# Power.net
KiCad netlist of a schematic drawn in Altium Designer
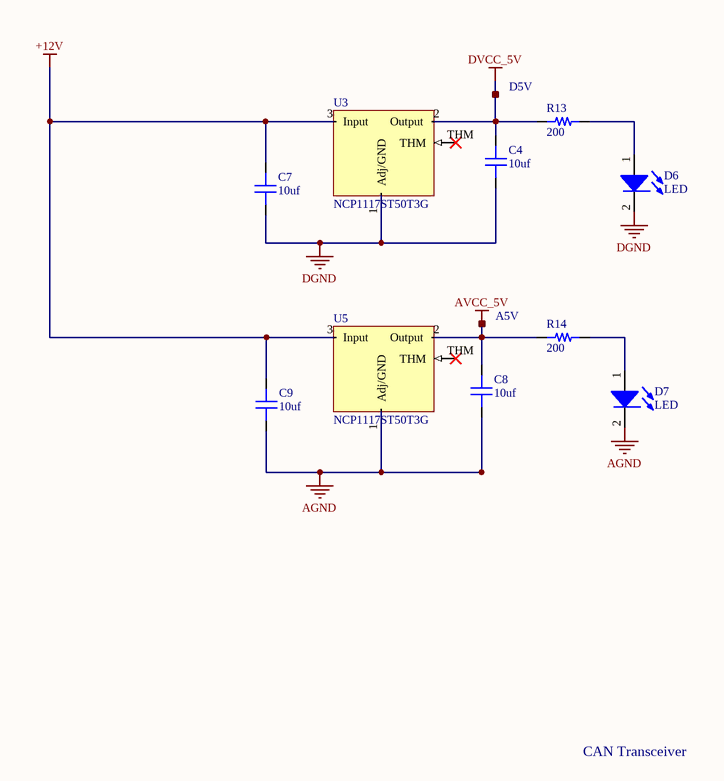
[diagram p0: Power.SchDoc]

(export (version "E")
  (design (tool "Eeschema 10.0.6"))
  (components
    (comp (ref "A5V") (value "RCU-0C") (footprint "RCU-0C") (libsource (lib "Altium-Lib") (part "RCU-0C")))
    (comp (ref "C4")
      (value "10uf")
      (footprint "CAP 0603/1608")
      (fields
        (field (name "Comment") "Capacitor MLCC 10uf 25V CAP 0603/1608")
        (field (name "CREATED_BY") "Nick Mah")
      )
      (libsource (lib "Altium-Lib") (part "Capacitor"))
    )
    (comp (ref "C7")
      (value "10uf")
      (footprint "CAP 0603/1608")
      (fields
        (field (name "Comment") "Capacitor MLCC 10uf 25V CAP 0603/1608")
        (field (name "CREATED_BY") "Nick Mah")
      )
      (libsource (lib "Altium-Lib") (part "Capacitor"))
    )
    (comp (ref "C8")
      (value "10uf")
      (footprint "CAP 0603/1608")
      (fields
        (field (name "Comment") "Capacitor MLCC 10uf 25V CAP 0603/1608")
        (field (name "CREATED_BY") "Nick Mah")
      )
      (libsource (lib "Altium-Lib") (part "Capacitor"))
    )
    (comp (ref "C9")
      (value "10uf")
      (footprint "CAP 0603/1608")
      (fields
        (field (name "Comment") "Capacitor MLCC 10uf 25V CAP 0603/1608")
        (field (name "CREATED_BY") "Nick Mah")
      )
      (libsource (lib "Altium-Lib") (part "Capacitor"))
    )
    (comp (ref "D5V") (value "RCU-0C") (footprint "RCU-0C") (libsource (lib "Altium-Lib") (part "RCU-0C")))
    (comp (ref "D6") (value "LED") (footprint "0805_LED") (libsource (lib "Altium-Lib") (part "LED")))
    (comp (ref "D7") (value "LED") (footprint "0805_LED") (libsource (lib "Altium-Lib") (part "LED")))
    (comp (ref "R13")
      (value "200")
      (footprint "RES 0603/1608")
      (fields
        (field (name "TOLERANCE") "5%")
        (field (name "POWER") "1/10W")
        (field (name "Comment") "Resistor 200 0603 1/10W 5%")
        (field (name "CREATED_BY") "Nick Mah")
      )
      (libsource (lib "Altium-Lib") (part "Resistor"))
    )
    (comp (ref "R14")
      (value "200")
      (footprint "RES 0603/1608")
      (fields
        (field (name "TOLERANCE") "5%")
        (field (name "POWER") "1/10W")
        (field (name "Comment") "Resistor 200 0603 1/10W 5%")
        (field (name "CREATED_BY") "Nick Mah")
      )
      (libsource (lib "Altium-Lib") (part "Resistor"))
    )
    (comp (ref "U3")
      (value "NCP1117ST50T3G")
      (footprint "SOT-223-3")
      (description "Linear Voltage Regulator IC Positive Fixed 1 Output 5V 1A SOT-223")
      (fields (field (name "CREATED_BY") "Angel Delgado"))
      (libsource (lib "Altium-Lib") (part "NCP1117ST50T3G"))
    )
    (comp (ref "U5")
      (value "NCP1117ST50T3G")
      (footprint "SOT-223-3")
      (description "Linear Voltage Regulator IC Positive Fixed 1 Output 5V 1A SOT-223")
      (fields (field (name "CREATED_BY") "Angel Delgado"))
      (libsource (lib "Altium-Lib") (part "NCP1117ST50T3G"))
    )
  )
  (nets
    (net (code "1") (name "+12V") (class "Default")
      (node (ref "C7") (pin "2") (pinfunction "2_2") (pintype "passive"))
      (node (ref "C9") (pin "2") (pinfunction "2_2") (pintype "passive"))
      (node (ref "U3") (pin "3") (pinfunction "Input_3") (pintype "input"))
      (node (ref "U5") (pin "3") (pinfunction "Input_3") (pintype "input"))
    )
    (net (code "2") (name "AGND") (class "Default")
      (node (ref "C8") (pin "1") (pinfunction "1_1") (pintype "passive"))
      (node (ref "C9") (pin "1") (pinfunction "1_1") (pintype "passive"))
      (node (ref "D7") (pin "2") (pinfunction "K_2") (pintype "passive"))
      (node (ref "U5") (pin "1") (pinfunction "Adj/GND_1") (pintype "input"))
    )
    (net (code "3") (name "AVCC_5V") (class "Default")
      (node (ref "A5V") (pin "1") (pintype "passive"))
      (node (ref "C8") (pin "2") (pinfunction "2_2") (pintype "passive"))
      (node (ref "R14") (pin "1") (pinfunction "1_1") (pintype "passive"))
      (node (ref "U5") (pin "2") (pinfunction "Output_2") (pintype "input"))
    )
    (net (code "4") (name "DGND") (class "Default")
      (node (ref "C4") (pin "1") (pinfunction "1_1") (pintype "passive"))
      (node (ref "C7") (pin "1") (pinfunction "1_1") (pintype "passive"))
      (node (ref "D6") (pin "2") (pinfunction "K_2") (pintype "passive"))
      (node (ref "U3") (pin "1") (pinfunction "Adj/GND_1") (pintype "input"))
    )
    (net (code "5") (name "DVCC_5V") (class "Default")
      (node (ref "C4") (pin "2") (pinfunction "2_2") (pintype "passive"))
      (node (ref "D5V") (pin "1") (pintype "passive"))
      (node (ref "R13") (pin "1") (pinfunction "1_1") (pintype "passive"))
      (node (ref "U3") (pin "2") (pinfunction "Output_2") (pintype "input"))
    )
    (net (code "6") (name "Net-(D6-A)") (class "Default")
      (node (ref "D6") (pin "1") (pinfunction "A_1") (pintype "passive"))
      (node (ref "R13") (pin "2") (pinfunction "2_2") (pintype "passive"))
    )
    (net (code "7") (name "Net-(D7-A)") (class "Default")
      (node (ref "D7") (pin "1") (pinfunction "A_1") (pintype "passive"))
      (node (ref "R14") (pin "2") (pinfunction "2_2") (pintype "passive"))
    )
    (net (code "8") (name "unconnected-(U3-PadTHM)") (class "Default")
      (node (ref "U3") (pin "THM") (pinfunction "THM_THM") (pintype "input+no_connect"))
    )
    (net (code "9") (name "unconnected-(U5-PadTHM)") (class "Default")
      (node (ref "U5") (pin "THM") (pinfunction "THM_THM") (pintype "input+no_connect"))
    )
  )
)
